# gpio.net
KiCad netlist of a schematic drawn in Altium Designer
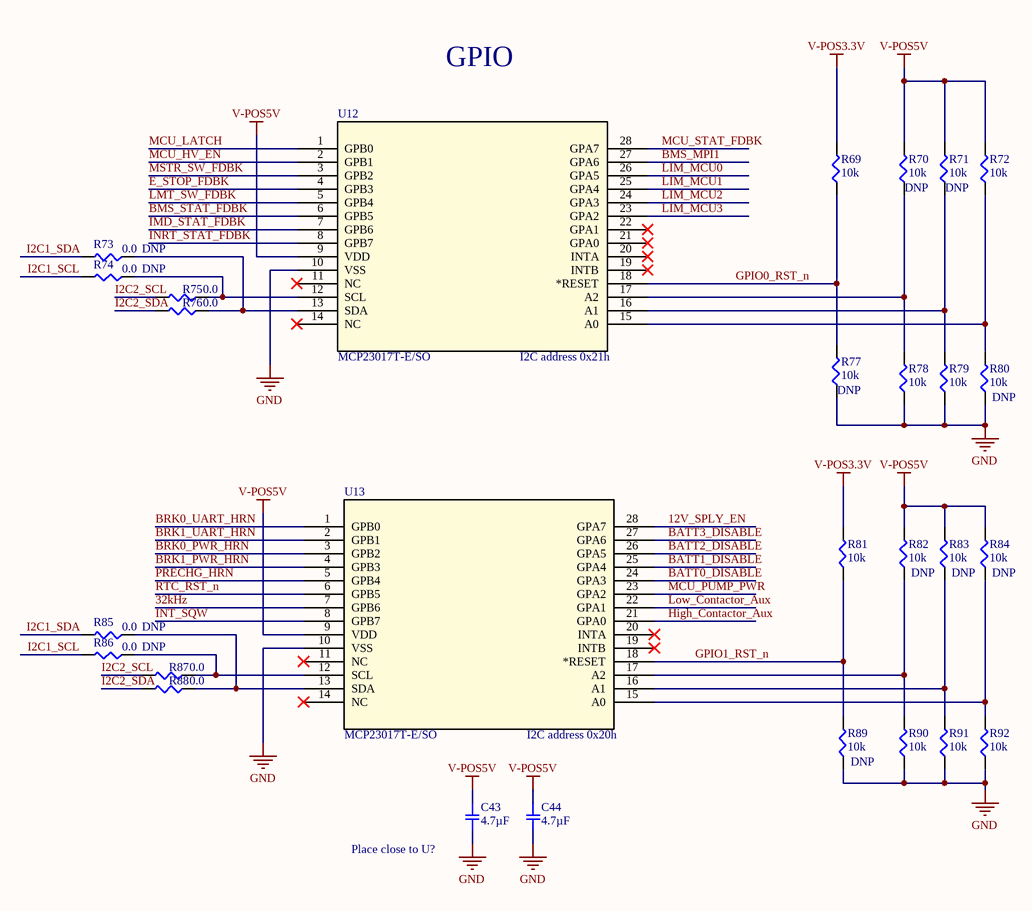
[diagram p0: gpio.SchDoc]

(export (version "E")
  (design (tool "Eeschema 10.0.6"))
  (components
    (comp (ref "C43")
      (value "4.7µF")
      (footprint "SMD-0805C")
      (description "CAP CER 4.7UF 6.3V X5R 0805")
      (fields
        (field (name "DIGI-KEY PART NUMBER") "490-9749-1-ND")
        (field (name "PART NUMBER") "GRM21BR60J475KA11L")
      )
      (libsource (lib "capacitor") (part "GRM21BR60J475KA11L"))
    )
    (comp (ref "C44")
      (value "4.7µF")
      (footprint "SMD-0805C")
      (description "CAP CER 4.7UF 6.3V X5R 0805")
      (fields
        (field (name "DIGI-KEY PART NUMBER") "490-9749-1-ND")
        (field (name "PART NUMBER") "GRM21BR60J475KA11L")
      )
      (libsource (lib "capacitor") (part "GRM21BR60J475KA11L"))
    )
    (comp (ref "R69")
      (value "10k")
      (footprint "SMD-0805-RES")
      (description "RES SMD 10K OHM 5% 1/2W 0805")
      (fields (field (name "PART NUMBER") "ERJ-P06J103V") (field (name "DIGI-KEY PART NUMBER") "P10KADCT-ND"))
      (libsource (lib "resistors") (part "ERJ-P06J103V"))
    )
    (comp (ref "R70")
      (value "10k")
      (footprint "SMD-0805-RES")
      (description "RES SMD 10K OHM 5% 1/2W 0805")
      (fields
        (field (name "PART NUMBER") "ERJ-P06J103V")
        (field (name "DIGI-KEY PART NUMBER") "P10KADCT-ND")
        (field (name "DNP") "DNP")
      )
      (libsource (lib "resistors") (part "ERJ-P06J103V"))
    )
    (comp (ref "R71")
      (value "10k")
      (footprint "SMD-0805-RES")
      (description "RES SMD 10K OHM 5% 1/2W 0805")
      (fields
        (field (name "PART NUMBER") "ERJ-P06J103V")
        (field (name "DIGI-KEY PART NUMBER") "P10KADCT-ND")
        (field (name "DNP") "DNP")
      )
      (libsource (lib "resistors") (part "ERJ-P06J103V"))
    )
    (comp (ref "R72")
      (value "10k")
      (footprint "SMD-0805-RES")
      (description "RES SMD 10K OHM 5% 1/2W 0805")
      (fields (field (name "PART NUMBER") "ERJ-P06J103V") (field (name "DIGI-KEY PART NUMBER") "P10KADCT-ND"))
      (libsource (lib "resistors") (part "ERJ-P06J103V"))
    )
    (comp (ref "R73")
      (value "0.0")
      (footprint "SMD-0805-RES")
      (description "RES SMD 0.0 OHM JUMPER 1/8W 0805")
      (fields
        (field (name "PART NUMBER") "ERJ-6GEY0R00V")
        (field (name "DIGI-KEY PART NUMBER") "P0.0ACT-ND")
        (field (name "DNP") "DNP")
      )
      (libsource (lib "resistors") (part "ERJ-6GEY0R00V"))
    )
    (comp (ref "R74")
      (value "0.0")
      (footprint "SMD-0805-RES")
      (description "RES SMD 0.0 OHM JUMPER 1/8W 0805")
      (fields
        (field (name "PART NUMBER") "ERJ-6GEY0R00V")
        (field (name "DIGI-KEY PART NUMBER") "P0.0ACT-ND")
        (field (name "DNP") "DNP")
      )
      (libsource (lib "resistors") (part "ERJ-6GEY0R00V"))
    )
    (comp (ref "R75")
      (value "0.0")
      (footprint "SMD-0805-RES")
      (description "RES SMD 0.0 OHM JUMPER 1/8W 0805")
      (fields (field (name "PART NUMBER") "ERJ-6GEY0R00V") (field (name "DIGI-KEY PART NUMBER") "P0.0ACT-ND"))
      (libsource (lib "resistors") (part "ERJ-6GEY0R00V"))
    )
    (comp (ref "R76")
      (value "0.0")
      (footprint "SMD-0805-RES")
      (description "RES SMD 0.0 OHM JUMPER 1/8W 0805")
      (fields (field (name "PART NUMBER") "ERJ-6GEY0R00V") (field (name "DIGI-KEY PART NUMBER") "P0.0ACT-ND"))
      (libsource (lib "resistors") (part "ERJ-6GEY0R00V"))
    )
    (comp (ref "R77")
      (value "10k")
      (footprint "SMD-0805-RES")
      (description "RES SMD 10K OHM 5% 1/2W 0805")
      (fields
        (field (name "PART NUMBER") "ERJ-P06J103V")
        (field (name "DIGI-KEY PART NUMBER") "P10KADCT-ND")
        (field (name "DNP") "DNP")
      )
      (libsource (lib "resistors") (part "ERJ-P06J103V"))
    )
    (comp (ref "R78")
      (value "10k")
      (footprint "SMD-0805-RES")
      (description "RES SMD 10K OHM 5% 1/2W 0805")
      (fields (field (name "PART NUMBER") "ERJ-P06J103V") (field (name "DIGI-KEY PART NUMBER") "P10KADCT-ND"))
      (libsource (lib "resistors") (part "ERJ-P06J103V"))
    )
    (comp (ref "R79")
      (value "10k")
      (footprint "SMD-0805-RES")
      (description "RES SMD 10K OHM 5% 1/2W 0805")
      (fields (field (name "PART NUMBER") "ERJ-P06J103V") (field (name "DIGI-KEY PART NUMBER") "P10KADCT-ND"))
      (libsource (lib "resistors") (part "ERJ-P06J103V"))
    )
    (comp (ref "R80")
      (value "10k")
      (footprint "SMD-0805-RES")
      (description "RES SMD 10K OHM 5% 1/2W 0805")
      (fields
        (field (name "PART NUMBER") "ERJ-P06J103V")
        (field (name "DIGI-KEY PART NUMBER") "P10KADCT-ND")
        (field (name "DNP") "DNP")
      )
      (libsource (lib "resistors") (part "ERJ-P06J103V"))
    )
    (comp (ref "R81")
      (value "10k")
      (footprint "SMD-0805-RES")
      (description "RES SMD 10K OHM 5% 1/2W 0805")
      (fields (field (name "PART NUMBER") "ERJ-P06J103V") (field (name "DIGI-KEY PART NUMBER") "P10KADCT-ND"))
      (libsource (lib "resistors") (part "ERJ-P06J103V"))
    )
    (comp (ref "R82")
      (value "10k")
      (footprint "SMD-0805-RES")
      (description "RES SMD 10K OHM 5% 1/2W 0805")
      (fields
        (field (name "PART NUMBER") "ERJ-P06J103V")
        (field (name "DIGI-KEY PART NUMBER") "P10KADCT-ND")
        (field (name "DNP") "DNP")
      )
      (libsource (lib "resistors") (part "ERJ-P06J103V"))
    )
    (comp (ref "R83")
      (value "10k")
      (footprint "SMD-0805-RES")
      (description "RES SMD 10K OHM 5% 1/2W 0805")
      (fields
        (field (name "PART NUMBER") "ERJ-P06J103V")
        (field (name "DIGI-KEY PART NUMBER") "P10KADCT-ND")
        (field (name "DNP") "DNP")
      )
      (libsource (lib "resistors") (part "ERJ-P06J103V"))
    )
    (comp (ref "R84")
      (value "10k")
      (footprint "SMD-0805-RES")
      (description "RES SMD 10K OHM 5% 1/2W 0805")
      (fields
        (field (name "PART NUMBER") "ERJ-P06J103V")
        (field (name "DIGI-KEY PART NUMBER") "P10KADCT-ND")
        (field (name "DNP") "DNP")
      )
      (libsource (lib "resistors") (part "ERJ-P06J103V"))
    )
    (comp (ref "R85")
      (value "0.0")
      (footprint "SMD-0805-RES")
      (description "RES SMD 0.0 OHM JUMPER 1/8W 0805")
      (fields
        (field (name "PART NUMBER") "ERJ-6GEY0R00V")
        (field (name "DIGI-KEY PART NUMBER") "P0.0ACT-ND")
        (field (name "DNP") "DNP")
      )
      (libsource (lib "resistors") (part "ERJ-6GEY0R00V"))
    )
    (comp (ref "R86")
      (value "0.0")
      (footprint "SMD-0805-RES")
      (description "RES SMD 0.0 OHM JUMPER 1/8W 0805")
      (fields
        (field (name "PART NUMBER") "ERJ-6GEY0R00V")
        (field (name "DIGI-KEY PART NUMBER") "P0.0ACT-ND")
        (field (name "DNP") "DNP")
      )
      (libsource (lib "resistors") (part "ERJ-6GEY0R00V"))
    )
    (comp (ref "R87")
      (value "0.0")
      (footprint "SMD-0805-RES")
      (description "RES SMD 0.0 OHM JUMPER 1/8W 0805")
      (fields (field (name "PART NUMBER") "ERJ-6GEY0R00V") (field (name "DIGI-KEY PART NUMBER") "P0.0ACT-ND"))
      (libsource (lib "resistors") (part "ERJ-6GEY0R00V"))
    )
    (comp (ref "R88")
      (value "0.0")
      (footprint "SMD-0805-RES")
      (description "RES SMD 0.0 OHM JUMPER 1/8W 0805")
      (fields (field (name "PART NUMBER") "ERJ-6GEY0R00V") (field (name "DIGI-KEY PART NUMBER") "P0.0ACT-ND"))
      (libsource (lib "resistors") (part "ERJ-6GEY0R00V"))
    )
    (comp (ref "R89")
      (value "10k")
      (footprint "SMD-0805-RES")
      (description "RES SMD 10K OHM 5% 1/2W 0805")
      (fields
        (field (name "PART NUMBER") "ERJ-P06J103V")
        (field (name "DIGI-KEY PART NUMBER") "P10KADCT-ND")
        (field (name "DNP") "DNP")
      )
      (libsource (lib "resistors") (part "ERJ-P06J103V"))
    )
    (comp (ref "R90")
      (value "10k")
      (footprint "SMD-0805-RES")
      (description "RES SMD 10K OHM 5% 1/2W 0805")
      (fields (field (name "PART NUMBER") "ERJ-P06J103V") (field (name "DIGI-KEY PART NUMBER") "P10KADCT-ND"))
      (libsource (lib "resistors") (part "ERJ-P06J103V"))
    )
    (comp (ref "R91")
      (value "10k")
      (footprint "SMD-0805-RES")
      (description "RES SMD 10K OHM 5% 1/2W 0805")
      (fields (field (name "PART NUMBER") "ERJ-P06J103V") (field (name "DIGI-KEY PART NUMBER") "P10KADCT-ND"))
      (libsource (lib "resistors") (part "ERJ-P06J103V"))
    )
    (comp (ref "R92")
      (value "10k")
      (footprint "SMD-0805-RES")
      (description "RES SMD 10K OHM 5% 1/2W 0805")
      (fields (field (name "PART NUMBER") "ERJ-P06J103V") (field (name "DIGI-KEY PART NUMBER") "P10KADCT-ND"))
      (libsource (lib "resistors") (part "ERJ-P06J103V"))
    )
    (comp (ref "U12")
      (value "MCP23017T-E/SO")
      (footprint "SOIC28-W_MC-M")
      (description "IC I/O EXPANDER I2C 16B 28SOIC")
      (fields (field (name "MANUFACTURER") "Microchip"))
      (libsource (lib "ic") (part "MCP23017T-E/SO"))
    )
    (comp (ref "U13")
      (value "MCP23017T-E/SO")
      (footprint "SOIC28-W_MC-M")
      (description "IC I/O EXPANDER I2C 16B 28SOIC")
      (fields (field (name "MANUFACTURER") "Microchip"))
      (libsource (lib "ic") (part "MCP23017T-E/SO"))
    )
  )
  (nets
    (net (code "1") (name "/12V_SPLY_EN") (class "Default")
      (node (ref "U13") (pin "28") (pinfunction "GPA7_28") (pintype "passive"))
    )
    (net (code "2") (name "/32kHz") (class "Default")
      (node (ref "U13") (pin "7") (pinfunction "GPB6_7") (pintype "passive"))
    )
    (net (code "3") (name "/BATT0_DISABLE") (class "Default")
      (node (ref "U13") (pin "24") (pinfunction "GPA3_24") (pintype "passive"))
    )
    (net (code "4") (name "/BATT1_DISABLE") (class "Default")
      (node (ref "U13") (pin "25") (pinfunction "GPA4_25") (pintype "passive"))
    )
    (net (code "5") (name "/BATT2_DISABLE") (class "Default")
      (node (ref "U13") (pin "26") (pinfunction "GPA5_26") (pintype "passive"))
    )
    (net (code "6") (name "/BATT3_DISABLE") (class "Default")
      (node (ref "U13") (pin "27") (pinfunction "GPA6_27") (pintype "passive"))
    )
    (net (code "7") (name "/BMS_MPI1") (class "Default")
      (node (ref "U12") (pin "27") (pinfunction "GPA6_27") (pintype "passive"))
    )
    (net (code "8") (name "/BMS_STAT_FDBK") (class "Default")
      (node (ref "U12") (pin "6") (pinfunction "GPB5_6") (pintype "passive"))
    )
    (net (code "9") (name "/BRK0_PWR_HRN") (class "Default")
      (node (ref "U13") (pin "3") (pinfunction "GPB2_3") (pintype "passive"))
    )
    (net (code "10") (name "/BRK0_UART_HRN") (class "Default")
      (node (ref "U13") (pin "1") (pinfunction "GPB0_1") (pintype "passive"))
    )
    (net (code "11") (name "/BRK1_PWR_HRN") (class "Default")
      (node (ref "U13") (pin "4") (pinfunction "GPB3_4") (pintype "passive"))
    )
    (net (code "12") (name "/BRK1_UART_HRN") (class "Default")
      (node (ref "U13") (pin "2") (pinfunction "GPB1_2") (pintype "passive"))
    )
    (net (code "13") (name "/E_STOP_FDBK") (class "Default")
      (node (ref "U12") (pin "4") (pinfunction "GPB3_4") (pintype "passive"))
    )
    (net (code "14") (name "/GPIO0_RST_n") (class "Default")
      (node (ref "R69") (pin "1") (pinfunction "1_1") (pintype "passive"))
      (node (ref "R77") (pin "2") (pinfunction "2_2") (pintype "passive"))
      (node (ref "U12") (pin "18") (pinfunction "*RESET_18") (pintype "passive"))
    )
    (net (code "15") (name "/GPIO1_RST_n") (class "Default")
      (node (ref "R81") (pin "1") (pinfunction "1_1") (pintype "passive"))
      (node (ref "R89") (pin "2") (pinfunction "2_2") (pintype "passive"))
      (node (ref "U13") (pin "18") (pinfunction "*RESET_18") (pintype "passive"))
    )
    (net (code "16") (name "/High_Contactor_Aux") (class "Default")
      (node (ref "U13") (pin "21") (pinfunction "GPA0_21") (pintype "passive"))
    )
    (net (code "17") (name "/I2C1_SCL") (class "Default")
      (node (ref "R74") (pin "2") (pinfunction "2_2") (pintype "passive"))
      (node (ref "R86") (pin "2") (pinfunction "2_2") (pintype "passive"))
    )
    (net (code "18") (name "/I2C1_SDA") (class "Default")
      (node (ref "R73") (pin "2") (pinfunction "2_2") (pintype "passive"))
      (node (ref "R85") (pin "2") (pinfunction "2_2") (pintype "passive"))
    )
    (net (code "19") (name "/I2C2_SCL") (class "Default")
      (node (ref "R75") (pin "2") (pinfunction "2_2") (pintype "passive"))
      (node (ref "R87") (pin "2") (pinfunction "2_2") (pintype "passive"))
    )
    (net (code "20") (name "/I2C2_SDA") (class "Default")
      (node (ref "R76") (pin "2") (pinfunction "2_2") (pintype "passive"))
      (node (ref "R88") (pin "2") (pinfunction "2_2") (pintype "passive"))
    )
    (net (code "21") (name "/IMD_STAT_FDBK") (class "Default")
      (node (ref "U12") (pin "7") (pinfunction "GPB6_7") (pintype "passive"))
    )
    (net (code "22") (name "/INRT_STAT_FDBK") (class "Default")
      (node (ref "U12") (pin "8") (pinfunction "GPB7_8") (pintype "passive"))
    )
    (net (code "23") (name "/INT_SQW") (class "Default")
      (node (ref "U13") (pin "8") (pinfunction "GPB7_8") (pintype "passive"))
    )
    (net (code "24") (name "/LIM_MCU0") (class "Default")
      (node (ref "U12") (pin "26") (pinfunction "GPA5_26") (pintype "passive"))
    )
    (net (code "25") (name "/LIM_MCU1") (class "Default")
      (node (ref "U12") (pin "25") (pinfunction "GPA4_25") (pintype "passive"))
    )
    (net (code "26") (name "/LIM_MCU2") (class "Default")
      (node (ref "U12") (pin "24") (pinfunction "GPA3_24") (pintype "passive"))
    )
    (net (code "27") (name "/LIM_MCU3") (class "Default")
      (node (ref "U12") (pin "23") (pinfunction "GPA2_23") (pintype "passive"))
    )
    (net (code "28") (name "/LMT_SW_FDBK") (class "Default")
      (node (ref "U12") (pin "5") (pinfunction "GPB4_5") (pintype "passive"))
    )
    (net (code "29") (name "/Low_Contactor_Aux") (class "Default")
      (node (ref "U13") (pin "22") (pinfunction "GPA1_22") (pintype "passive"))
    )
    (net (code "30") (name "/MCU_HV_EN") (class "Default")
      (node (ref "U12") (pin "2") (pinfunction "GPB1_2") (pintype "passive"))
    )
    (net (code "31") (name "/MCU_LATCH") (class "Default")
      (node (ref "U12") (pin "1") (pinfunction "GPB0_1") (pintype "passive"))
    )
    (net (code "32") (name "/MCU_PUMP_PWR") (class "Default")
      (node (ref "U13") (pin "23") (pinfunction "GPA2_23") (pintype "passive"))
    )
    (net (code "33") (name "/MCU_STAT_FDBK") (class "Default")
      (node (ref "U12") (pin "28") (pinfunction "GPA7_28") (pintype "passive"))
    )
    (net (code "34") (name "/MSTR_SW_FDBK") (class "Default")
      (node (ref "U12") (pin "3") (pinfunction "GPB2_3") (pintype "passive"))
    )
    (net (code "35") (name "/PRECHG_HRN") (class "Default")
      (node (ref "U13") (pin "5") (pinfunction "GPB4_5") (pintype "passive"))
    )
    (net (code "36") (name "/RTC_RST_n") (class "Default")
      (node (ref "U13") (pin "6") (pinfunction "GPB5_6") (pintype "passive"))
    )
    (net (code "37") (name "GND") (class "Default")
      (node (ref "C43") (pin "2") (pinfunction "2_2") (pintype "passive"))
      (node (ref "C44") (pin "2") (pinfunction "2_2") (pintype "passive"))
      (node (ref "R77") (pin "1") (pinfunction "1_1") (pintype "passive"))
      (node (ref "R78") (pin "1") (pinfunction "1_1") (pintype "passive"))
      (node (ref "R79") (pin "1") (pinfunction "1_1") (pintype "passive"))
      (node (ref "R80") (pin "1") (pinfunction "1_1") (pintype "passive"))
      (node (ref "R89") (pin "1") (pinfunction "1_1") (pintype "passive"))
      (node (ref "R90") (pin "1") (pinfunction "1_1") (pintype "passive"))
      (node (ref "R91") (pin "1") (pinfunction "1_1") (pintype "passive"))
      (node (ref "R92") (pin "1") (pinfunction "1_1") (pintype "passive"))
      (node (ref "U12") (pin "10") (pinfunction "VSS_10") (pintype "passive"))
      (node (ref "U13") (pin "10") (pinfunction "VSS_10") (pintype "passive"))
    )
    (net (code "38") (name "Net-(U12-A0)") (class "Default")
      (node (ref "R72") (pin "1") (pinfunction "1_1") (pintype "passive"))
      (node (ref "R80") (pin "2") (pinfunction "2_2") (pintype "passive"))
      (node (ref "U12") (pin "15") (pinfunction "A0_15") (pintype "passive"))
    )
    (net (code "39") (name "Net-(U12-A1)") (class "Default")
      (node (ref "R71") (pin "1") (pinfunction "1_1") (pintype "passive"))
      (node (ref "R79") (pin "2") (pinfunction "2_2") (pintype "passive"))
      (node (ref "U12") (pin "16") (pinfunction "A1_16") (pintype "passive"))
    )
    (net (code "40") (name "Net-(U12-A2)") (class "Default")
      (node (ref "R70") (pin "1") (pinfunction "1_1") (pintype "passive"))
      (node (ref "R78") (pin "2") (pinfunction "2_2") (pintype "passive"))
      (node (ref "U12") (pin "17") (pinfunction "A2_17") (pintype "passive"))
    )
    (net (code "41") (name "Net-(U12-SCL)") (class "Default")
      (node (ref "R74") (pin "1") (pinfunction "1_1") (pintype "passive"))
      (node (ref "R75") (pin "1") (pinfunction "1_1") (pintype "passive"))
      (node (ref "U12") (pin "12") (pinfunction "SCL_12") (pintype "passive"))
    )
    (net (code "42") (name "Net-(U12-SDA)") (class "Default")
      (node (ref "R73") (pin "1") (pinfunction "1_1") (pintype "passive"))
      (node (ref "R76") (pin "1") (pinfunction "1_1") (pintype "passive"))
      (node (ref "U12") (pin "13") (pinfunction "SDA_13") (pintype "passive"))
    )
    (net (code "43") (name "Net-(U13-A0)") (class "Default")
      (node (ref "R84") (pin "1") (pinfunction "1_1") (pintype "passive"))
      (node (ref "R92") (pin "2") (pinfunction "2_2") (pintype "passive"))
      (node (ref "U13") (pin "15") (pinfunction "A0_15") (pintype "passive"))
    )
    (net (code "44") (name "Net-(U13-A1)") (class "Default")
      (node (ref "R83") (pin "1") (pinfunction "1_1") (pintype "passive"))
      (node (ref "R91") (pin "2") (pinfunction "2_2") (pintype "passive"))
      (node (ref "U13") (pin "16") (pinfunction "A1_16") (pintype "passive"))
    )
    (net (code "45") (name "Net-(U13-A2)") (class "Default")
      (node (ref "R82") (pin "1") (pinfunction "1_1") (pintype "passive"))
      (node (ref "R90") (pin "2") (pinfunction "2_2") (pintype "passive"))
      (node (ref "U13") (pin "17") (pinfunction "A2_17") (pintype "passive"))
    )
    (net (code "46") (name "Net-(U13-SCL)") (class "Default")
      (node (ref "R86") (pin "1") (pinfunction "1_1") (pintype "passive"))
      (node (ref "R87") (pin "1") (pinfunction "1_1") (pintype "passive"))
      (node (ref "U13") (pin "12") (pinfunction "SCL_12") (pintype "passive"))
    )
    (net (code "47") (name "Net-(U13-SDA)") (class "Default")
      (node (ref "R85") (pin "1") (pinfunction "1_1") (pintype "passive"))
      (node (ref "R88") (pin "1") (pinfunction "1_1") (pintype "passive"))
      (node (ref "U13") (pin "13") (pinfunction "SDA_13") (pintype "passive"))
    )
    (net (code "48") (name "V-POS3.3V") (class "Default")
      (node (ref "R69") (pin "2") (pinfunction "2_2") (pintype "passive"))
      (node (ref "R81") (pin "2") (pinfunction "2_2") (pintype "passive"))
    )
    (net (code "49") (name "V-POS5V") (class "Default")
      (node (ref "C43") (pin "1") (pinfunction "1_1") (pintype "passive"))
      (node (ref "C44") (pin "1") (pinfunction "1_1") (pintype "passive"))
      (node (ref "R70") (pin "2") (pinfunction "2_2") (pintype "passive"))
      (node (ref "R71") (pin "2") (pinfunction "2_2") (pintype "passive"))
      (node (ref "R72") (pin "2") (pinfunction "2_2") (pintype "passive"))
      (node (ref "R82") (pin "2") (pinfunction "2_2") (pintype "passive"))
      (node (ref "R83") (pin "2") (pinfunction "2_2") (pintype "passive"))
      (node (ref "R84") (pin "2") (pinfunction "2_2") (pintype "passive"))
      (node (ref "U12") (pin "9") (pinfunction "VDD_9") (pintype "passive"))
      (node (ref "U13") (pin "9") (pinfunction "VDD_9") (pintype "passive"))
    )
    (net (code "50") (name "unconnected-(U12-GPA0-Pad21)") (class "Default")
      (node (ref "U12") (pin "21") (pinfunction "GPA0_21") (pintype "passive+no_connect"))
    )
    (net (code "51") (name "unconnected-(U12-GPA1-Pad22)") (class "Default")
      (node (ref "U12") (pin "22") (pinfunction "GPA1_22") (pintype "passive+no_connect"))
    )
    (net (code "52") (name "unconnected-(U12-INTA-Pad20)") (class "Default")
      (node (ref "U12") (pin "20") (pinfunction "INTA_20") (pintype "passive+no_connect"))
    )
    (net (code "53") (name "unconnected-(U12-INTB-Pad19)") (class "Default")
      (node (ref "U12") (pin "19") (pinfunction "INTB_19") (pintype "passive+no_connect"))
    )
    (net (code "54") (name "unconnected-(U12-NC-Pad11)") (class "Default")
      (node (ref "U12") (pin "11") (pinfunction "NC_11") (pintype "passive+no_connect"))
    )
    (net (code "55") (name "unconnected-(U12-NC-Pad14)") (class "Default")
      (node (ref "U12") (pin "14") (pinfunction "NC_14") (pintype "passive+no_connect"))
    )
    (net (code "56") (name "unconnected-(U13-INTA-Pad20)") (class "Default")
      (node (ref "U13") (pin "20") (pinfunction "INTA_20") (pintype "passive+no_connect"))
    )
    (net (code "57") (name "unconnected-(U13-INTB-Pad19)") (class "Default")
      (node (ref "U13") (pin "19") (pinfunction "INTB_19") (pintype "passive+no_connect"))
    )
    (net (code "58") (name "unconnected-(U13-NC-Pad11)") (class "Default")
      (node (ref "U13") (pin "11") (pinfunction "NC_11") (pintype "passive+no_connect"))
    )
    (net (code "59") (name "unconnected-(U13-NC-Pad14)") (class "Default")
      (node (ref "U13") (pin "14") (pinfunction "NC_14") (pintype "passive+no_connect"))
    )
  )
)
